# zxuno_rev_mcleod.net
KiCad netlist of a schematic drawn in EAGLE
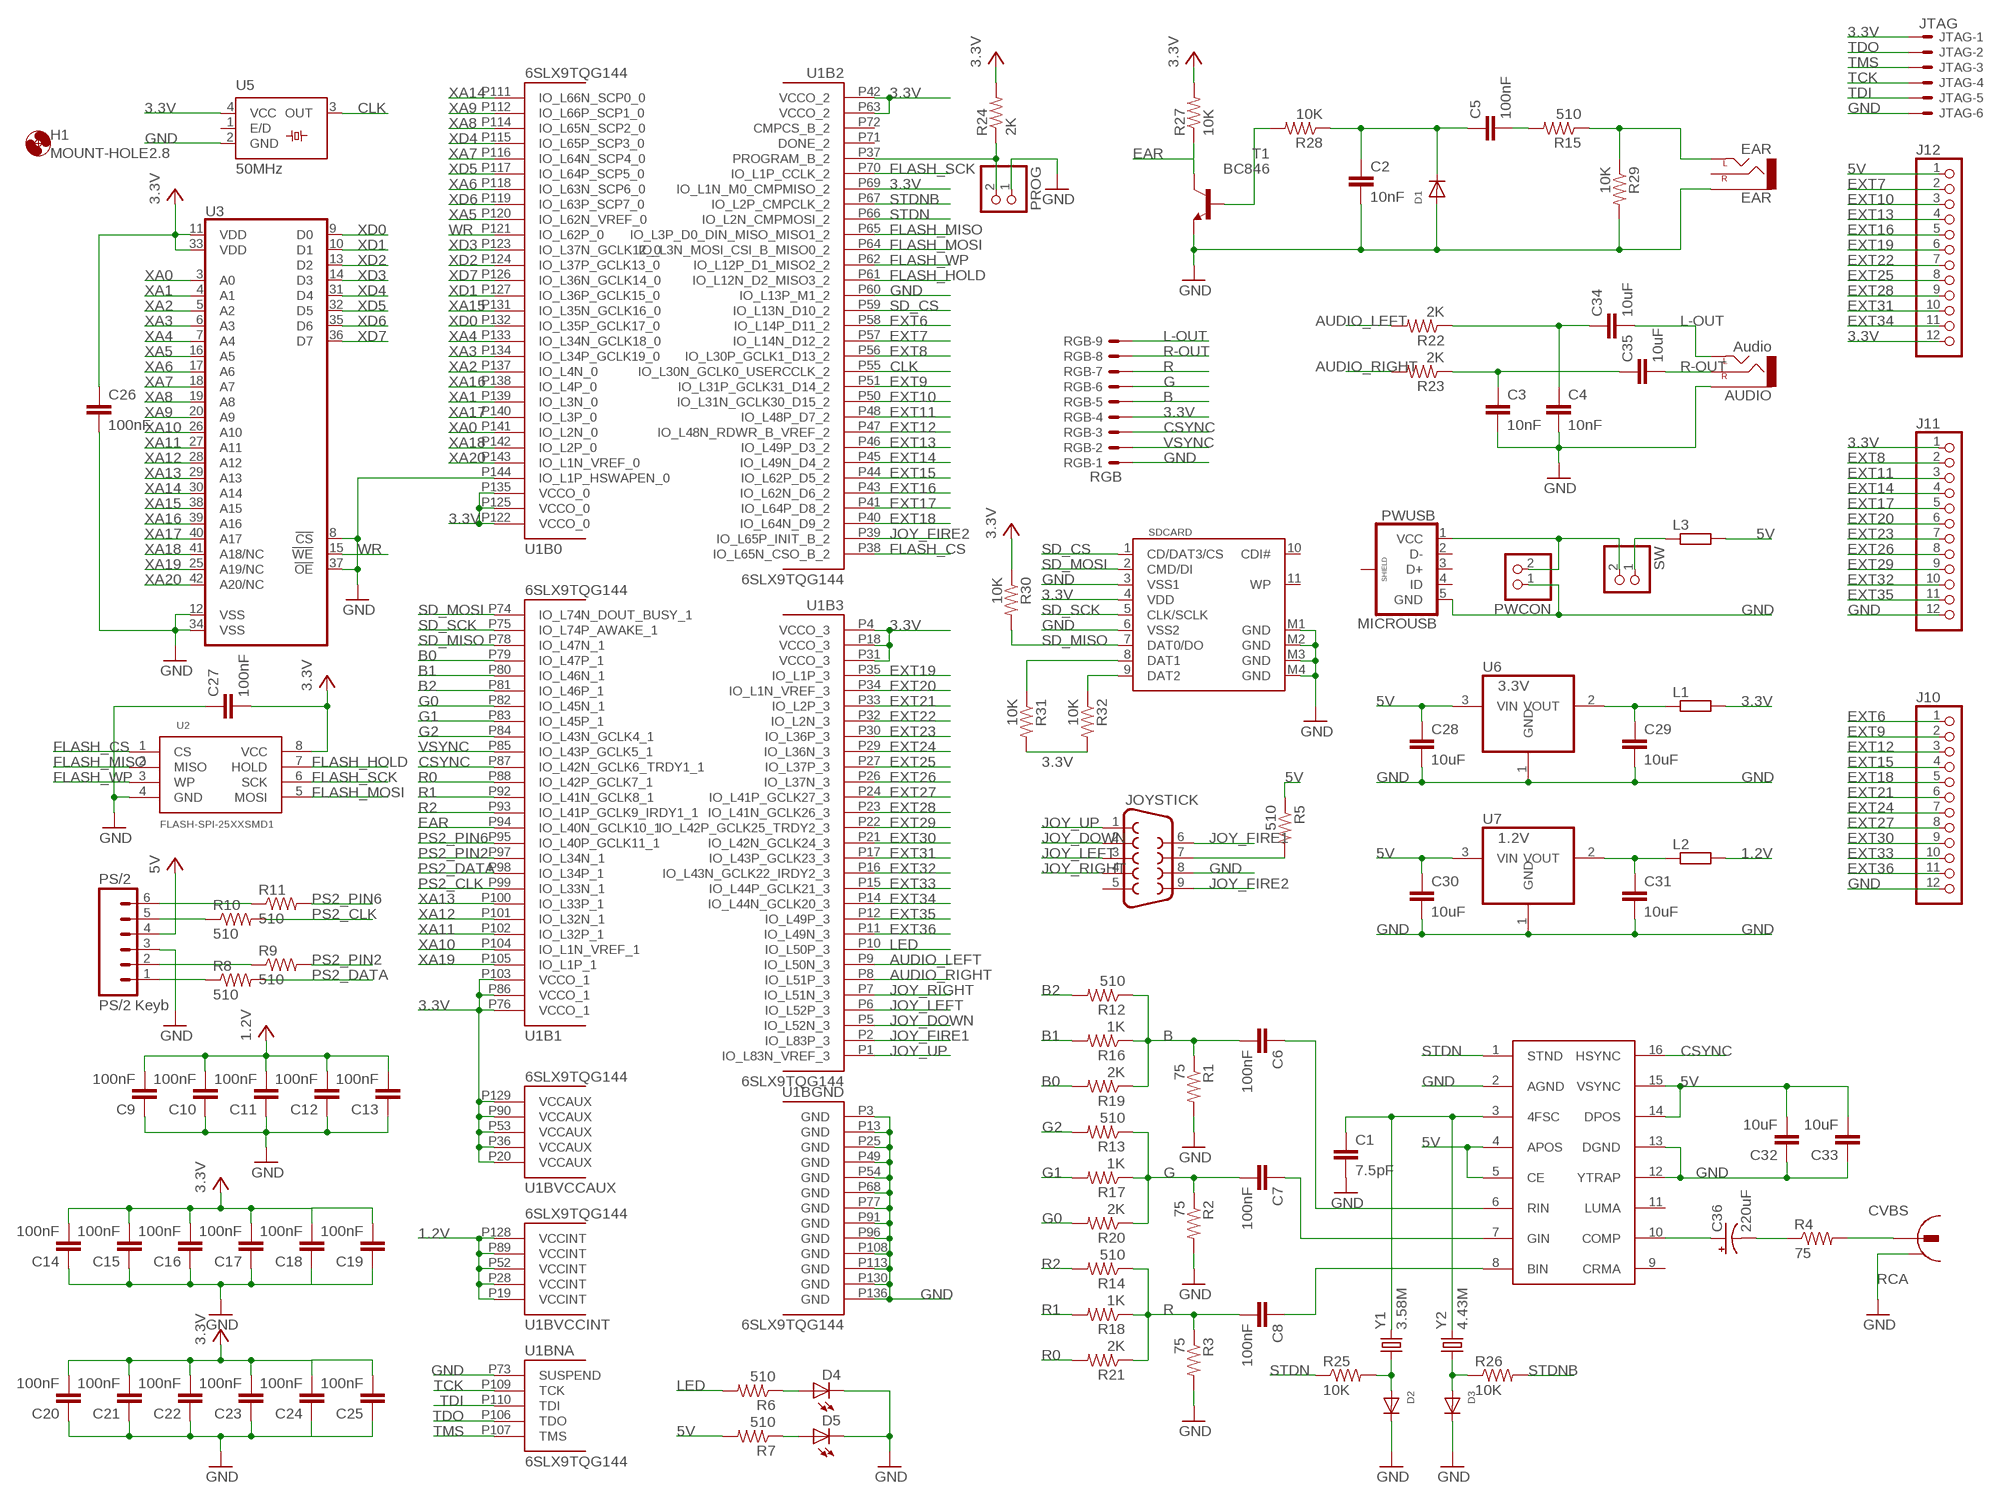
[diagram p0: schematic, sheet 1]

(export (version "E")
  (design (tool "Eeschema 10.0.6"))
  (components
    (comp (ref "AUDIO")
      (value "Audio")
      (footprint "eagle-import:AUDIO-JACK")
      (libsource (lib "eagle-import") (part "AUDIO-JACKPTH"))
    )
    (comp (ref "C1")
      (value "7.5pF")
      (footprint "eagle-import:C0805")
      (libsource (lib "eagle-import") (part "C-EUC0805"))
    )
    (comp (ref "C2")
      (value "10nF")
      (footprint "eagle-import:C0805")
      (libsource (lib "eagle-import") (part "C-EUC0805"))
    )
    (comp (ref "C3")
      (value "10nF")
      (footprint "eagle-import:C0805")
      (libsource (lib "eagle-import") (part "C-EUC0805"))
    )
    (comp (ref "C4")
      (value "10nF")
      (footprint "eagle-import:C0805")
      (libsource (lib "eagle-import") (part "C-EUC0805"))
    )
    (comp (ref "C5")
      (value "100nF")
      (footprint "eagle-import:C0603")
      (libsource (lib "eagle-import") (part "C-EUC0603"))
    )
    (comp (ref "C6")
      (value "100nF")
      (footprint "eagle-import:C0603")
      (libsource (lib "eagle-import") (part "C-EUC0603"))
    )
    (comp (ref "C7")
      (value "100nF")
      (footprint "eagle-import:C0603")
      (libsource (lib "eagle-import") (part "C-EUC0603"))
    )
    (comp (ref "C8")
      (value "100nF")
      (footprint "eagle-import:C0603")
      (libsource (lib "eagle-import") (part "C-EUC0603"))
    )
    (comp (ref "C9")
      (value "100nF")
      (footprint "eagle-import:C0603")
      (libsource (lib "eagle-import") (part "C-EUC0603"))
    )
    (comp (ref "C10")
      (value "100nF")
      (footprint "eagle-import:C0603")
      (libsource (lib "eagle-import") (part "C-EUC0603"))
    )
    (comp (ref "C11")
      (value "100nF")
      (footprint "eagle-import:C0603")
      (libsource (lib "eagle-import") (part "C-EUC0603"))
    )
    (comp (ref "C12")
      (value "100nF")
      (footprint "eagle-import:C0603")
      (libsource (lib "eagle-import") (part "C-EUC0603"))
    )
    (comp (ref "C13")
      (value "100nF")
      (footprint "eagle-import:C0603")
      (libsource (lib "eagle-import") (part "C-EUC0603"))
    )
    (comp (ref "C14")
      (value "100nF")
      (footprint "eagle-import:C0603")
      (libsource (lib "eagle-import") (part "C-EUC0603"))
    )
    (comp (ref "C15")
      (value "100nF")
      (footprint "eagle-import:C0603")
      (libsource (lib "eagle-import") (part "C-EUC0603"))
    )
    (comp (ref "C16")
      (value "100nF")
      (footprint "eagle-import:C0603")
      (libsource (lib "eagle-import") (part "C-EUC0603"))
    )
    (comp (ref "C17")
      (value "100nF")
      (footprint "eagle-import:C0603")
      (libsource (lib "eagle-import") (part "C-EUC0603"))
    )
    (comp (ref "C18")
      (value "100nF")
      (footprint "eagle-import:C0603")
      (libsource (lib "eagle-import") (part "C-EUC0603"))
    )
    (comp (ref "C19")
      (value "100nF")
      (footprint "eagle-import:C0603")
      (libsource (lib "eagle-import") (part "C-EUC0603"))
    )
    (comp (ref "C20")
      (value "100nF")
      (footprint "eagle-import:C0603")
      (libsource (lib "eagle-import") (part "C-EUC0603"))
    )
    (comp (ref "C21")
      (value "100nF")
      (footprint "eagle-import:C0603")
      (libsource (lib "eagle-import") (part "C-EUC0603"))
    )
    (comp (ref "C22")
      (value "100nF")
      (footprint "eagle-import:C0603")
      (libsource (lib "eagle-import") (part "C-EUC0603"))
    )
    (comp (ref "C23")
      (value "100nF")
      (footprint "eagle-import:C0603")
      (libsource (lib "eagle-import") (part "C-EUC0603"))
    )
    (comp (ref "C24")
      (value "100nF")
      (footprint "eagle-import:C0603")
      (libsource (lib "eagle-import") (part "C-EUC0603"))
    )
    (comp (ref "C25")
      (value "100nF")
      (footprint "eagle-import:C0603")
      (libsource (lib "eagle-import") (part "C-EUC0603"))
    )
    (comp (ref "C26")
      (value "100nF")
      (footprint "eagle-import:C0603")
      (libsource (lib "eagle-import") (part "C-EUC0603"))
    )
    (comp (ref "C27")
      (value "100nF")
      (footprint "eagle-import:C0603")
      (libsource (lib "eagle-import") (part "C-EUC0603"))
    )
    (comp (ref "C28")
      (value "10uF")
      (footprint "eagle-import:C0805")
      (libsource (lib "eagle-import") (part "C-EUC0805"))
    )
    (comp (ref "C29")
      (value "10uF")
      (footprint "eagle-import:C0805")
      (libsource (lib "eagle-import") (part "C-EUC0805"))
    )
    (comp (ref "C30")
      (value "10uF")
      (footprint "eagle-import:C0805")
      (libsource (lib "eagle-import") (part "C-EUC0805"))
    )
    (comp (ref "C31")
      (value "10uF")
      (footprint "eagle-import:C0805")
      (libsource (lib "eagle-import") (part "C-EUC0805"))
    )
    (comp (ref "C32")
      (value "10uF")
      (footprint "eagle-import:C0805")
      (libsource (lib "eagle-import") (part "C-EUC0805"))
    )
    (comp (ref "C33")
      (value "10uF")
      (footprint "eagle-import:C0805")
      (libsource (lib "eagle-import") (part "C-EUC0805"))
    )
    (comp (ref "C34")
      (value "10uF")
      (footprint "eagle-import:C0805")
      (libsource (lib "eagle-import") (part "C-EUC0805"))
    )
    (comp (ref "C35")
      (value "10uF")
      (footprint "eagle-import:C0805")
      (libsource (lib "eagle-import") (part "C-EUC0805"))
    )
    (comp (ref "C36")
      (value "220uF")
      (footprint "eagle-import:153CLV-0605")
      (libsource (lib "eagle-import") (part "CPOL-US153CLV-0605"))
    )
    (comp (ref "CVBS")
      (value "RCA")
      (footprint "eagle-import:RCA_JACK_RCJ-04X_-_DUPLICATE_1PRIMARY")
      (libsource (lib "eagle-import") (part "RCA_JACK_RCJ-04X_-_DUPLICATE_1"))
    )
    (comp (ref "D1")
      (value "DIODESOD-523")
      (footprint "eagle-import:SOD-523")
      (libsource (lib "eagle-import") (part "DIODESOD-523"))
    )
    (comp (ref "D2")
      (value "DIODESOD-523")
      (footprint "eagle-import:SOD-523")
      (libsource (lib "eagle-import") (part "DIODESOD-523"))
    )
    (comp (ref "D3")
      (value "DIODESOD-523")
      (footprint "eagle-import:SOD-523")
      (libsource (lib "eagle-import") (part "DIODESOD-523"))
    )
    (comp (ref "D4")
      (value "LEDCHIP-LED0805")
      (footprint "eagle-import:CHIP-LED0805")
      (libsource (lib "eagle-import") (part "LEDCHIP-LED0805"))
    )
    (comp (ref "D5")
      (value "LEDCHIP-LED0805")
      (footprint "eagle-import:CHIP-LED0805")
      (libsource (lib "eagle-import") (part "LEDCHIP-LED0805"))
    )
    (comp (ref "EAR")
      (value "EAR")
      (footprint "eagle-import:AUDIO-JACK")
      (libsource (lib "eagle-import") (part "AUDIO-JACKPTH"))
    )
    (comp (ref "H1")
      (value "MOUNT-HOLE2.8")
      (footprint "eagle-import:2,8")
      (libsource (lib "eagle-import") (part "MOUNT-HOLE2.8"))
    )
    (comp (ref "J10")
      (value "PINHD-1X12")
      (footprint "eagle-import:1X12")
      (libsource (lib "eagle-import") (part "PINHD-1X12"))
    )
    (comp (ref "J11")
      (value "PINHD-1X12")
      (footprint "eagle-import:1X12")
      (libsource (lib "eagle-import") (part "PINHD-1X12"))
    )
    (comp (ref "J12")
      (value "PINHD-1X12")
      (footprint "eagle-import:1X12")
      (libsource (lib "eagle-import") (part "PINHD-1X12"))
    )
    (comp (ref "JOYSTICK")
      (value "DB9MALE")
      (footprint "eagle-import:DB9_MALE")
      (libsource (lib "eagle-import") (part "DB9MALE"))
    )
    (comp (ref "JTAG")
      (value "JTAG")
      (footprint "eagle-import:53047-06")
      (fields (field (name "MPN") "53047-0610-C"))
      (libsource (lib "eagle-import") (part "53?-06047"))
    )
    (comp (ref "L1")
      (value "R-EU_M0805")
      (footprint "eagle-import:M0805")
      (libsource (lib "eagle-import") (part "R-EU_M0805"))
    )
    (comp (ref "L2")
      (value "R-EU_M0805")
      (footprint "eagle-import:M0805")
      (libsource (lib "eagle-import") (part "R-EU_M0805"))
    )
    (comp (ref "L3")
      (value "R-EU_M0805")
      (footprint "eagle-import:M0805")
      (libsource (lib "eagle-import") (part "R-EU_M0805"))
    )
    (comp (ref "PROG")
      (value "PINHD-1X2")
      (footprint "eagle-import:1X02")
      (libsource (lib "eagle-import") (part "PINHD-1X2"))
    )
    (comp (ref "PS/2")
      (value "PS/2 Keyb")
      (footprint "eagle-import:DINC_MIN_TM_6_1PRIMARY")
      (libsource (lib "eagle-import") (part "DINC_MIN_TM_6_1"))
    )
    (comp (ref "PWCON")
      (value "PINHD-1X2")
      (footprint "eagle-import:1X02")
      (libsource (lib "eagle-import") (part "PINHD-1X2"))
    )
    (comp (ref "PWUSB")
      (value "MICROUSB")
      (footprint "eagle-import:MICRO_USB_1PRIMARY")
      (libsource (lib "eagle-import") (part "MICROUSB"))
    )
    (comp (ref "R1")
      (value "75")
      (footprint "eagle-import:M0805")
      (libsource (lib "eagle-import") (part "R-US_M0805"))
    )
    (comp (ref "R2")
      (value "75")
      (footprint "eagle-import:M0805")
      (libsource (lib "eagle-import") (part "R-US_M0805"))
    )
    (comp (ref "R3")
      (value "75")
      (footprint "eagle-import:M0805")
      (libsource (lib "eagle-import") (part "R-US_M0805"))
    )
    (comp (ref "R4")
      (value "75")
      (footprint "eagle-import:M0805")
      (libsource (lib "eagle-import") (part "R-US_M0805"))
    )
    (comp (ref "R5")
      (value "510")
      (footprint "eagle-import:M0805")
      (libsource (lib "eagle-import") (part "R-US_M0805"))
    )
    (comp (ref "R6")
      (value "510")
      (footprint "eagle-import:M0805")
      (libsource (lib "eagle-import") (part "R-US_M0805"))
    )
    (comp (ref "R7")
      (value "510")
      (footprint "eagle-import:M0805")
      (libsource (lib "eagle-import") (part "R-US_M0805"))
    )
    (comp (ref "R8")
      (value "510")
      (footprint "eagle-import:M0805")
      (libsource (lib "eagle-import") (part "R-US_M0805"))
    )
    (comp (ref "R9")
      (value "510")
      (footprint "eagle-import:M0805")
      (libsource (lib "eagle-import") (part "R-US_M0805"))
    )
    (comp (ref "R10")
      (value "510")
      (footprint "eagle-import:M0805")
      (libsource (lib "eagle-import") (part "R-US_M0805"))
    )
    (comp (ref "R11")
      (value "510")
      (footprint "eagle-import:M0805")
      (libsource (lib "eagle-import") (part "R-US_M0805"))
    )
    (comp (ref "R12")
      (value "510")
      (footprint "eagle-import:M0805")
      (libsource (lib "eagle-import") (part "R-US_M0805"))
    )
    (comp (ref "R13")
      (value "510")
      (footprint "eagle-import:M0805")
      (libsource (lib "eagle-import") (part "R-US_M0805"))
    )
    (comp (ref "R14")
      (value "510")
      (footprint "eagle-import:M0805")
      (libsource (lib "eagle-import") (part "R-US_M0805"))
    )
    (comp (ref "R15")
      (value "510")
      (footprint "eagle-import:M0805")
      (libsource (lib "eagle-import") (part "R-US_M0805"))
    )
    (comp (ref "R16")
      (value "1K")
      (footprint "eagle-import:M0805")
      (libsource (lib "eagle-import") (part "R-US_M0805"))
    )
    (comp (ref "R17")
      (value "1K")
      (footprint "eagle-import:M0805")
      (libsource (lib "eagle-import") (part "R-US_M0805"))
    )
    (comp (ref "R18")
      (value "1K")
      (footprint "eagle-import:M0805")
      (libsource (lib "eagle-import") (part "R-US_M0805"))
    )
    (comp (ref "R19")
      (value "2K")
      (footprint "eagle-import:M0805")
      (libsource (lib "eagle-import") (part "R-US_M0805"))
    )
    (comp (ref "R20")
      (value "2K")
      (footprint "eagle-import:M0805")
      (libsource (lib "eagle-import") (part "R-US_M0805"))
    )
    (comp (ref "R21")
      (value "2K")
      (footprint "eagle-import:M0805")
      (libsource (lib "eagle-import") (part "R-US_M0805"))
    )
    (comp (ref "R22")
      (value "2K")
      (footprint "eagle-import:M0805")
      (libsource (lib "eagle-import") (part "R-US_M0805"))
    )
    (comp (ref "R23")
      (value "2K")
      (footprint "eagle-import:M0805")
      (libsource (lib "eagle-import") (part "R-US_M0805"))
    )
    (comp (ref "R24")
      (value "2K")
      (footprint "eagle-import:M0805")
      (libsource (lib "eagle-import") (part "R-US_M0805"))
    )
    (comp (ref "R25")
      (value "10K")
      (footprint "eagle-import:M0805")
      (libsource (lib "eagle-import") (part "R-US_M0805"))
    )
    (comp (ref "R26")
      (value "10K")
      (footprint "eagle-import:M0805")
      (libsource (lib "eagle-import") (part "R-US_M0805"))
    )
    (comp (ref "R27")
      (value "10K")
      (footprint "eagle-import:M0805")
      (libsource (lib "eagle-import") (part "R-US_M0805"))
    )
    (comp (ref "R28")
      (value "10K")
      (footprint "eagle-import:M0805")
      (libsource (lib "eagle-import") (part "R-US_M0805"))
    )
    (comp (ref "R29")
      (value "10K")
      (footprint "eagle-import:M0805")
      (libsource (lib "eagle-import") (part "R-US_M0805"))
    )
    (comp (ref "R30")
      (value "10K")
      (footprint "eagle-import:M0805")
      (libsource (lib "eagle-import") (part "R-US_M0805"))
    )
    (comp (ref "R31")
      (value "10K")
      (footprint "eagle-import:M0805")
      (libsource (lib "eagle-import") (part "R-US_M0805"))
    )
    (comp (ref "R32")
      (value "10K")
      (footprint "eagle-import:M0805")
      (libsource (lib "eagle-import") (part "R-US_M0805"))
    )
    (comp (ref "RGB")
      (value "RGB")
      (footprint "eagle-import:53048-09")
      (fields (field (name "MPN") "53048-0910"))
      (libsource (lib "eagle-import") (part "53?-09048"))
    )
    (comp (ref "SDCARD")
      (value "SDCARD")
      (footprint "eagle-import:SDCMF-10915W010")
      (libsource (lib "eagle-import") (part "SDCARD"))
    )
    (comp (ref "SW")
      (value "PINHD-1X2")
      (footprint "eagle-import:1X02")
      (libsource (lib "eagle-import") (part "PINHD-1X2"))
    )
    (comp (ref "T1")
      (value "BC846")
      (footprint "eagle-import:SOT23")
      (libsource (lib "eagle-import") (part "BC846"))
    )
    (comp (ref "U1")
      (value "6SLX9TQG144")
      (footprint "eagle-import:TQ144")
      (libsource (lib "eagle-import") (part "6SLX9TQG144"))
    )
    (comp (ref "U2")
      (value "FLASH-SPI-25XXSMD1")
      (footprint "eagle-import:SO08-EIAJ")
      (libsource (lib "eagle-import") (part "FLASH-SPI-25XXSMD1"))
    )
    (comp (ref "U3")
      (value "ISSI_SRAM_8BIT")
      (footprint "eagle-import:TSOP44-II")
      (libsource (lib "eagle-import") (part "ISSI_SRAM_8BIT"))
    )
    (comp (ref "U4")
      (value "AD724")
      (footprint "eagle-import:SO16W")
      (libsource (lib "eagle-import") (part "AD725"))
    )
    (comp (ref "U5")
      (value "50MHz")
      (footprint "eagle-import:SM_OSC_1PRIMARY")
      (libsource (lib "eagle-import") (part "SM_OSC_1"))
    )
    (comp (ref "U6")
      (value "3.3V")
      (footprint "eagle-import:SOT223")
      (fields (field (name "MPN") "REG1117"))
      (libsource (lib "eagle-import") (part "REG1117"))
    )
    (comp (ref "U7")
      (value "1.2V")
      (footprint "eagle-import:SOT223")
      (fields (field (name "MPN") "REG1117"))
      (libsource (lib "eagle-import") (part "REG1117"))
    )
    (comp (ref "Y1")
      (value "3.58M")
      (footprint "eagle-import:HC49UP")
      (libsource (lib "eagle-import") (part "CRYSTALHC49UP"))
    )
    (comp (ref "Y2")
      (value "4.43M")
      (footprint "eagle-import:HC49UP")
      (libsource (lib "eagle-import") (part "CRYSTALHC49UP"))
    )
  )
  (nets
    (net (code "1") (name "/AUDIO_LEFT") (class "Default")
      (node (ref "R22") (pin "2") (pinfunction "2_2") (pintype "passive"))
      (node (ref "U1") (pin "P9") (pinfunction "IO_L50N_3_P9") (pintype "bidirectional"))
    )
    (net (code "2") (name "/AUDIO_RIGHT") (class "Default")
      (node (ref "R23") (pin "2") (pinfunction "2_2") (pintype "passive"))
      (node (ref "U1") (pin "P8") (pinfunction "IO_L51P_3_P8") (pintype "bidirectional"))
    )
    (net (code "3") (name "/B") (class "Default")
      (node (ref "C6") (pin "2") (pinfunction "2_2") (pintype "passive"))
      (node (ref "R1") (pin "1") (pinfunction "1_1") (pintype "passive"))
      (node (ref "R12") (pin "1") (pinfunction "1_1") (pintype "passive"))
      (node (ref "R16") (pin "1") (pinfunction "1_1") (pintype "passive"))
      (node (ref "R19") (pin "1") (pinfunction "1_1") (pintype "passive"))
      (node (ref "RGB") (pin "5") (pinfunction "S_5") (pintype "passive"))
    )
    (net (code "4") (name "/B0") (class "Default")
      (node (ref "R19") (pin "2") (pinfunction "2_2") (pintype "passive"))
      (node (ref "U1") (pin "P79") (pinfunction "IO_L47P_1_P79") (pintype "bidirectional"))
    )
    (net (code "5") (name "/B1") (class "Default")
      (node (ref "R16") (pin "2") (pinfunction "2_2") (pintype "passive"))
      (node (ref "U1") (pin "P80") (pinfunction "IO_L46N_1_P80") (pintype "bidirectional"))
    )
    (net (code "6") (name "/B2") (class "Default")
      (node (ref "R12") (pin "2") (pinfunction "2_2") (pintype "passive"))
      (node (ref "U1") (pin "P81") (pinfunction "IO_L46P_1_P81") (pintype "bidirectional"))
    )
    (net (code "7") (name "/CLK") (class "Default")
      (node (ref "U1") (pin "P55") (pinfunction "IO_L30N_GCLK0_USERCCLK_2_P55") (pintype "bidirectional"))
      (node (ref "U5") (pin "3") (pinfunction "OUT_3") (pintype "output"))
    )
    (net (code "8") (name "/CSYNC") (class "Default")
      (node (ref "RGB") (pin "3") (pinfunction "S_3") (pintype "passive"))
      (node (ref "U1") (pin "P87") (pinfunction "IO_L42N_GCLK6_TRDY1_1_P87") (pintype "bidirectional"))
      (node (ref "U4") (pin "16") (pinfunction "HSYNC_16") (pintype "bidirectional"))
    )
    (net (code "9") (name "/EAR") (class "Default")
      (node (ref "R27") (pin "1") (pinfunction "1_1") (pintype "passive"))
      (node (ref "T1") (pin "3") (pinfunction "C_3") (pintype "passive"))
      (node (ref "U1") (pin "P94") (pinfunction "IO_L40N_GCLK10_1_P94") (pintype "bidirectional"))
    )
    (net (code "10") (name "/EXT6") (class "Default")
      (node (ref "J10") (pin "1") (pinfunction "1_1") (pintype "passive"))
      (node (ref "U1") (pin "P58") (pinfunction "IO_L14P_D11_2_P58") (pintype "bidirectional"))
    )
    (net (code "11") (name "/EXT7") (class "Default")
      (node (ref "J12") (pin "2") (pinfunction "2_2") (pintype "passive"))
      (node (ref "U1") (pin "P57") (pinfunction "IO_L14N_D12_2_P57") (pintype "bidirectional"))
    )
    (net (code "12") (name "/EXT8") (class "Default")
      (node (ref "J11") (pin "2") (pinfunction "2_2") (pintype "passive"))
      (node (ref "U1") (pin "P56") (pinfunction "IO_L30P_GCLK1_D13_2_P56") (pintype "bidirectional"))
    )
    (net (code "13") (name "/EXT9") (class "Default")
      (node (ref "J10") (pin "2") (pinfunction "2_2") (pintype "passive"))
      (node (ref "U1") (pin "P51") (pinfunction "IO_L31P_GCLK31_D14_2_P51") (pintype "bidirectional"))
    )
    (net (code "14") (name "/EXT10") (class "Default")
      (node (ref "J12") (pin "3") (pinfunction "3_3") (pintype "passive"))
      (node (ref "U1") (pin "P50") (pinfunction "IO_L31N_GCLK30_D15_2_P50") (pintype "bidirectional"))
    )
    (net (code "15") (name "/EXT11") (class "Default")
      (node (ref "J11") (pin "3") (pinfunction "3_3") (pintype "passive"))
      (node (ref "U1") (pin "P48") (pinfunction "IO_L48P_D7_2_P48") (pintype "bidirectional"))
    )
    (net (code "16") (name "/EXT12") (class "Default")
      (node (ref "J10") (pin "3") (pinfunction "3_3") (pintype "passive"))
      (node (ref "U1") (pin "P47") (pinfunction "IO_L48N_RDWR_B_VREF_2_P47") (pintype "bidirectional"))
    )
    (net (code "17") (name "/EXT13") (class "Default")
      (node (ref "J12") (pin "4") (pinfunction "4_4") (pintype "passive"))
      (node (ref "U1") (pin "P46") (pinfunction "IO_L49P_D3_2_P46") (pintype "bidirectional"))
    )
    (net (code "18") (name "/EXT14") (class "Default")
      (node (ref "J11") (pin "4") (pinfunction "4_4") (pintype "passive"))
      (node (ref "U1") (pin "P45") (pinfunction "IO_L49N_D4_2_P45") (pintype "bidirectional"))
    )
    (net (code "19") (name "/EXT15") (class "Default")
      (node (ref "J10") (pin "4") (pinfunction "4_4") (pintype "passive"))
      (node (ref "U1") (pin "P44") (pinfunction "IO_L62P_D5_2_P44") (pintype "bidirectional"))
    )
    (net (code "20") (name "/EXT16") (class "Default")
      (node (ref "J12") (pin "5") (pinfunction "5_5") (pintype "passive"))
      (node (ref "U1") (pin "P43") (pinfunction "IO_L62N_D6_2_P43") (pintype "bidirectional"))
    )
    (net (code "21") (name "/EXT17") (class "Default")
      (node (ref "J11") (pin "5") (pinfunction "5_5") (pintype "passive"))
      (node (ref "U1") (pin "P41") (pinfunction "IO_L64P_D8_2_P41") (pintype "bidirectional"))
    )
    (net (code "22") (name "/EXT18") (class "Default")
      (node (ref "J10") (pin "5") (pinfunction "5_5") (pintype "passive"))
      (node (ref "U1") (pin "P40") (pinfunction "IO_L64N_D9_2_P40") (pintype "bidirectional"))
    )
    (net (code "23") (name "/EXT19") (class "Default")
      (node (ref "J12") (pin "6") (pinfunction "6_6") (pintype "passive"))
      (node (ref "U1") (pin "P35") (pinfunction "IO_L1P_3_P35") (pintype "bidirectional"))
    )
    (net (code "24") (name "/EXT20") (class "Default")
      (node (ref "J11") (pin "6") (pinfunction "6_6") (pintype "passive"))
      (node (ref "U1") (pin "P34") (pinfunction "IO_L1N_VREF_3_P34") (pintype "bidirectional"))
    )
    (net (code "25") (name "/EXT21") (class "Default")
      (node (ref "J10") (pin "6") (pinfunction "6_6") (pintype "passive"))
      (node (ref "U1") (pin "P33") (pinfunction "IO_L2P_3_P33") (pintype "bidirectional"))
    )
    (net (code "26") (name "/EXT22") (class "Default")
      (node (ref "J12") (pin "7") (pinfunction "7_7") (pintype "passive"))
      (node (ref "U1") (pin "P32") (pinfunction "IO_L2N_3_P32") (pintype "bidirectional"))
    )
    (net (code "27") (name "/EXT23") (class "Default")
      (node (ref "J11") (pin "7") (pinfunction "7_7") (pintype "passive"))
      (node (ref "U1") (pin "P30") (pinfunction "IO_L36P_3_P30") (pintype "bidirectional"))
    )
    (net (code "28") (name "/EXT24") (class "Default")
      (node (ref "J10") (pin "7") (pinfunction "7_7") (pintype "passive"))
      (node (ref "U1") (pin "P29") (pinfunction "IO_L36N_3_P29") (pintype "bidirectional"))
    )
    (net (code "29") (name "/EXT25") (class "Default")
      (node (ref "J12") (pin "8") (pinfunction "8_8") (pintype "passive"))
      (node (ref "U1") (pin "P27") (pinfunction "IO_L37P_3_P27") (pintype "bidirectional"))
    )
    (net (code "30") (name "/EXT26") (class "Default")
      (node (ref "J11") (pin "8") (pinfunction "8_8") (pintype "passive"))
      (node (ref "U1") (pin "P26") (pinfunction "IO_L37N_3_P26") (pintype "bidirectional"))
    )
    (net (code "31") (name "/EXT27") (class "Default")
      (node (ref "J10") (pin "8") (pinfunction "8_8") (pintype "passive"))
      (node (ref "U1") (pin "P24") (pinfunction "IO_L41P_GCLK27_3_P24") (pintype "bidirectional"))
    )
    (net (code "32") (name "/EXT28") (class "Default")
      (node (ref "J12") (pin "9") (pinfunction "9_9") (pintype "passive"))
      (node (ref "U1") (pin "P23") (pinfunction "IO_L41N_GCLK26_3_P23") (pintype "bidirectional"))
    )
    (net (code "33") (name "/EXT29") (class "Default")
      (node (ref "J11") (pin "9") (pinfunction "9_9") (pintype "passive"))
      (node (ref "U1") (pin "P22") (pinfunction "IO_L42P_GCLK25_TRDY2_3_P22") (pintype "bidirectional"))
    )
    (net (code "34") (name "/EXT30") (class "Default")
      (node (ref "J10") (pin "9") (pinfunction "9_9") (pintype "passive"))
      (node (ref "U1") (pin "P21") (pinfunction "IO_L42N_GCLK24_3_P21") (pintype "bidirectional"))
    )
    (net (code "35") (name "/EXT31") (class "Default")
      (node (ref "J12") (pin "10") (pinfunction "10_10") (pintype "passive"))
      (node (ref "U1") (pin "P17") (pinfunction "IO_L43P_GCLK23_3_P17") (pintype "bidirectional"))
    )
    (net (code "36") (name "/EXT32") (class "Default")
      (node (ref "J11") (pin "10") (pinfunction "10_10") (pintype "passive"))
      (node (ref "U1") (pin "P16") (pinfunction "IO_L43N_GCLK22_IRDY2_3_P16") (pintype "bidirectional"))
    )
    (net (code "37") (name "/EXT33") (class "Default")
      (node (ref "J10") (pin "10") (pinfunction "10_10") (pintype "passive"))
      (node (ref "U1") (pin "P15") (pinfunction "IO_L44P_GCLK21_3_P15") (pintype "bidirectional"))
    )
    (net (code "38") (name "/EXT34") (class "Default")
      (node (ref "J12") (pin "11") (pinfunction "11_11") (pintype "passive"))
      (node (ref "U1") (pin "P14") (pinfunction "IO_L44N_GCLK20_3_P14") (pintype "bidirectional"))
    )
    (net (code "39") (name "/EXT35") (class "Default")
      (node (ref "J11") (pin "11") (pinfunction "11_11") (pintype "passive"))
      (node (ref "U1") (pin "P12") (pinfunction "IO_L49P_3_P12") (pintype "bidirectional"))
    )
    (net (code "40") (name "/EXT36") (class "Default")
      (node (ref "J10") (pin "11") (pinfunction "11_11") (pintype "passive"))
      (node (ref "U1") (pin "P11") (pinfunction "IO_L49N_3_P11") (pintype "bidirectional"))
    )
    (net (code "41") (name "/FLASH_CS") (class "Default")
      (node (ref "U1") (pin "P38") (pinfunction "IO_L65N_CSO_B_2_P38") (pintype "bidirectional"))
      (node (ref "U2") (pin "1") (pinfunction "CS_1") (pintype "bidirectional"))
    )
    (net (code "42") (name "/FLASH_HOLD") (class "Default")
      (node (ref "U1") (pin "P61") (pinfunction "IO_L12N_D2_MISO3_2_P61") (pintype "bidirectional"))
      (node (ref "U2") (pin "7") (pinfunction "HOLD_7") (pintype "bidirectional"))
    )
    (net (code "43") (name "/FLASH_MISO") (class "Default")
      (node (ref "U1") (pin "P65") (pinfunction "IO_L3P_D0_DIN_MISO_MISO1_2_P65") (pintype "bidirectional"))
      (node (ref "U2") (pin "2") (pinfunction "MISO_2") (pintype "bidirectional"))
    )
    (net (code "44") (name "/FLASH_MOSI") (class "Default")
      (node (ref "U1") (pin "P64") (pinfunction "IO_L3N_MOSI_CSI_B_MISO0_2_P64") (pintype "bidirectional"))
      (node (ref "U2") (pin "5") (pinfunction "MOSI_5") (pintype "bidirectional"))
    )
    (net (code "45") (name "/FLASH_SCK") (class "Default")
      (node (ref "U1") (pin "P70") (pinfunction "IO_L1P_CCLK_2_P70") (pintype "bidirectional"))
      (node (ref "U2") (pin "6") (pinfunction "SCK_6") (pintype "bidirectional"))
    )
    (net (code "46") (name "/FLASH_WP") (class "Default")
      (node (ref "U1") (pin "P62") (pinfunction "IO_L12P_D1_MISO2_2_P62") (pintype "bidirectional"))
      (node (ref "U2") (pin "3") (pinfunction "WP_3") (pintype "bidirectional"))
    )
    (net (code "47") (name "/G") (class "Default")
      (node (ref "C7") (pin "2") (pinfunction "2_2") (pintype "passive"))
      (node (ref "R13") (pin "1") (pinfunction "1_1") (pintype "passive"))
      (node (ref "R17") (pin "1") (pinfunction "1_1") (pintype "passive"))
      (node (ref "R2") (pin "1") (pinfunction "1_1") (pintype "passive"))
      (node (ref "R20") (pin "1") (pinfunction "1_1") (pintype "passive"))
      (node (ref "RGB") (pin "6") (pinfunction "S_6") (pintype "passive"))
    )
    (net (code "48") (name "/G0") (class "Default")
      (node (ref "R20") (pin "2") (pinfunction "2_2") (pintype "passive"))
      (node (ref "U1") (pin "P82") (pinfunction "IO_L45N_1_P82") (pintype "bidirectional"))
    )
    (net (code "49") (name "/G1") (class "Default")
      (node (ref "R17") (pin "2") (pinfunction "2_2") (pintype "passive"))
      (node (ref "U1") (pin "P83") (pinfunction "IO_L45P_1_P83") (pintype "bidirectional"))
    )
    (net (code "50") (name "/G2") (class "Default")
      (node (ref "R13") (pin "2") (pinfunction "2_2") (pintype "passive"))
      (node (ref "U1") (pin "P84") (pinfunction "IO_L43N_GCLK4_1_P84") (pintype "bidirectional"))
    )
    (net (code "51") (name "/JOY_DOWN") (class "Default")
      (node (ref "JOYSTICK") (pin "2") (pinfunction "2_2") (pintype "passive"))
      (node (ref "U1") (pin "P5") (pinfunction "IO_L52N_3_P5") (pintype "bidirectional"))
    )
    (net (code "52") (name "/JOY_FIRE1") (class "Default")
      (node (ref "JOYSTICK") (pin "6") (pinfunction "6_6") (pintype "passive"))
      (node (ref "U1") (pin "P2") (pinfunction "IO_L83P_3_P2") (pintype "bidirectional"))
    )
    (net (code "53") (name "/JOY_FIRE2") (class "Default")
      (node (ref "JOYSTICK") (pin "9") (pinfunction "9_9") (pintype "passive"))
      (node (ref "U1") (pin "P39") (pinfunction "IO_L65P_INIT_B_2_P39") (pintype "bidirectional"))
    )
    (net (code "54") (name "/JOY_LEFT") (class "Default")
      (node (ref "JOYSTICK") (pin "3") (pinfunction "3_3") (pintype "passive"))
      (node (ref "U1") (pin "P6") (pinfunction "IO_L52P_3_P6") (pintype "bidirectional"))
    )
    (net (code "55") (name "/JOY_RIGHT") (class "Default")
      (node (ref "JOYSTICK") (pin "4") (pinfunction "4_4") (pintype "passive"))
      (node (ref "U1") (pin "P7") (pinfunction "IO_L51N_3_P7") (pintype "bidirectional"))
    )
    (net (code "56") (name "/JOY_UP") (class "Default")
      (node (ref "JOYSTICK") (pin "1") (pinfunction "1_1") (pintype "passive"))
      (node (ref "U1") (pin "P1") (pinfunction "IO_L83N_VREF_3_P1") (pintype "bidirectional"))
    )
    (net (code "57") (name "/L-OUT") (class "Default")
      (node (ref "AUDIO") (pin "TIP") (pinfunction "LEFT_TIP") (pintype "bidirectional"))
      (node (ref "C34") (pin "2") (pinfunction "2_2") (pintype "passive"))
      (node (ref "RGB") (pin "9") (pinfunction "S_9") (pintype "passive"))
    )
    (net (code "58") (name "/LED") (class "Default")
      (node (ref "R6") (pin "2") (pinfunction "2_2") (pintype "passive"))
      (node (ref "U1") (pin "P10") (pinfunction "IO_L50P_3_P10") (pintype "bidirectional"))
    )
    (net (code "59") (name "/PS2_CLK") (class "Default")
      (node (ref "R10") (pin "2") (pinfunction "2_2") (pintype "passive"))
      (node (ref "U1") (pin "P99") (pinfunction "IO_L33N_1_P99") (pintype "bidirectional"))
    )
    (net (code "60") (name "/PS2_DATA") (class "Default")
      (node (ref "R8") (pin "2") (pinfunction "2_2") (pintype "passive"))
      (node (ref "U1") (pin "P98") (pinfunction "IO_L34P_1_P98") (pintype "bidirectional"))
    )
    (net (code "61") (name "/PS2_PIN2") (class "Default")
      (node (ref "R9") (pin "2") (pinfunction "2_2") (pintype "passive"))
      (node (ref "U1") (pin "P97") (pinfunction "IO_L34N_1_P97") (pintype "bidirectional"))
    )
    (net (code "62") (name "/PS2_PIN6") (class "Default")
      (node (ref "R11") (pin "2") (pinfunction "2_2") (pintype "passive"))
      (node (ref "U1") (pin "P95") (pinfunction "IO_L40P_GCLK11_1_P95") (pintype "bidirectional"))
    )
    (net (code "63") (name "/R") (class "Default")
      (node (ref "C8") (pin "2") (pinfunction "2_2") (pintype "passive"))
      (node (ref "R14") (pin "1") (pinfunction "1_1") (pintype "passive"))
      (node (ref "R18") (pin "1") (pinfunction "1_1") (pintype "passive"))
      (node (ref "R21") (pin "1") (pinfunction "1_1") (pintype "passive"))
      (node (ref "R3") (pin "1") (pinfunction "1_1") (pintype "passive"))
      (node (ref "RGB") (pin "7") (pinfunction "S_7") (pintype "passive"))
    )
    (net (code "64") (name "/R-OUT") (class "Default")
      (node (ref "AUDIO") (pin "RING") (pinfunction "RIGHT_RING") (pintype "bidirectional"))
      (node (ref "C35") (pin "2") (pinfunction "2_2") (pintype "passive"))
      (node (ref "RGB") (pin "8") (pinfunction "S_8") (pintype "passive"))
    )
    (net (code "65") (name "/R0") (class "Default")
      (node (ref "R21") (pin "2") (pinfunction "2_2") (pintype "passive"))
      (node (ref "U1") (pin "P88") (pinfunction "IO_L42P_GCLK7_1_P88") (pintype "bidirectional"))
    )
    (net (code "66") (name "/R1") (class "Default")
      (node (ref "R18") (pin "2") (pinfunction "2_2") (pintype "passive"))
      (node (ref "U1") (pin "P92") (pinfunction "IO_L41N_GCLK8_1_P92") (pintype "bidirectional"))
    )
    (net (code "67") (name "/R2") (class "Default")
      (node (ref "R14") (pin "2") (pinfunction "2_2") (pintype "passive"))
      (node (ref "U1") (pin "P93") (pinfunction "IO_L41P_GCLK9_IRDY1_1_P93") (pintype "bidirectional"))
    )
    (net (code "68") (name "/SD_CS") (class "Default")
      (node (ref "SDCARD") (pin "1") (pinfunction "CD/DAT3/CS_1") (pintype "bidirectional"))
      (node (ref "U1") (pin "P59") (pinfunction "IO_L13N_D10_2_P59") (pintype "bidirectional"))
    )
    (net (code "69") (name "/SD_MISO") (class "Default")
      (node (ref "R30") (pin "2") (pinfunction "2_2") (pintype "passive"))
      (node (ref "SDCARD") (pin "7") (pinfunction "DAT0/DO_7") (pintype "bidirectional"))
      (node (ref "U1") (pin "P78") (pinfunction "IO_L47N_1_P78") (pintype "bidirectional"))
    )
    (net (code "70") (name "/SD_MOSI") (class "Default")
      (node (ref "SDCARD") (pin "2") (pinfunction "CMD/DI_2") (pintype "bidirectional"))
      (node (ref "U1") (pin "P74") (pinfunction "IO_L74N_DOUT_BUSY_1_P74") (pintype "bidirectional"))
    )
    (net (code "71") (name "/SD_SCK") (class "Default")
      (node (ref "SDCARD") (pin "5") (pinfunction "CLK/SCLK_5") (pintype "bidirectional"))
      (node (ref "U1") (pin "P75") (pinfunction "IO_L74P_AWAKE_1_P75") (pintype "bidirectional"))
    )
    (net (code "72") (name "/STDN") (class "Default")
      (node (ref "R25") (pin "1") (pinfunction "1_1") (pintype "passive"))
      (node (ref "U1") (pin "P66") (pinfunction "IO_L2N_CMPMOSI_2_P66") (pintype "bidirectional"))
      (node (ref "U4") (pin "1") (pinfunction "STND_1") (pintype "bidirectional"))
    )
    (net (code "73") (name "/STDNB") (class "Default")
      (node (ref "R26") (pin "2") (pinfunction "2_2") (pintype "passive"))
      (node (ref "U1") (pin "P67") (pinfunction "IO_L2P_CMPCLK_2_P67") (pintype "bidirectional"))
    )
    (net (code "74") (name "/TCK") (class "Default")
      (node (ref "JTAG") (pin "4") (pinfunction "S_4") (pintype "passive"))
      (node (ref "U1") (pin "P109") (pinfunction "TCK_P109") (pintype "input"))
    )
    (net (code "75") (name "/TDI") (class "Default")
      (node (ref "JTAG") (pin "5") (pinfunction "S_5") (pintype "passive"))
      (node (ref "U1") (pin "P110") (pinfunction "TDI_P110") (pintype "input"))
    )
    (net (code "76") (name "/TDO") (class "Default")
      (node (ref "JTAG") (pin "2") (pinfunction "S_2") (pintype "passive"))
      (node (ref "U1") (pin "P106") (pinfunction "TDO_P106") (pintype "output"))
    )
    (net (code "77") (name "/TMS") (class "Default")
      (node (ref "JTAG") (pin "3") (pinfunction "S_3") (pintype "passive"))
      (node (ref "U1") (pin "P107") (pinfunction "TMS_P107") (pintype "input"))
    )
    (net (code "78") (name "/VSYNC") (class "Default")
      (node (ref "RGB") (pin "2") (pinfunction "S_2") (pintype "passive"))
      (node (ref "U1") (pin "P85") (pinfunction "IO_L43P_GCLK5_1_P85") (pintype "bidirectional"))
    )
    (net (code "79") (name "/WR") (class "Default")
      (node (ref "U1") (pin "P121") (pinfunction "IO_L62P_0_P121") (pintype "bidirectional"))
      (node (ref "U3") (pin "15") (pinfunction "~{WE}_15") (pintype "input"))
    )
    (net (code "80") (name "/XA0") (class "Default")
      (node (ref "U1") (pin "P141") (pinfunction "IO_L2N_0_P141") (pintype "bidirectional"))
      (node (ref "U3") (pin "3") (pinfunction "A0_3") (pintype "input"))
    )
    (net (code "81") (name "/XA1") (class "Default")
      (node (ref "U1") (pin "P139") (pinfunction "IO_L3N_0_P139") (pintype "bidirectional"))
      (node (ref "U3") (pin "4") (pinfunction "A1_4") (pintype "input"))
    )
    (net (code "82") (name "/XA2") (class "Default")
      (node (ref "U1") (pin "P137") (pinfunction "IO_L4N_0_P137") (pintype "bidirectional"))
      (node (ref "U3") (pin "5") (pinfunction "A2_5") (pintype "input"))
    )
    (net (code "83") (name "/XA3") (class "Default")
      (node (ref "U1") (pin "P134") (pinfunction "IO_L34P_GCLK19_0_P134") (pintype "bidirectional"))
      (node (ref "U3") (pin "6") (pinfunction "A3_6") (pintype "input"))
    )
    (net (code "84") (name "/XA4") (class "Default")
      (node (ref "U1") (pin "P133") (pinfunction "IO_L34N_GCLK18_0_P133") (pintype "bidirectional"))
      (node (ref "U3") (pin "7") (pinfunction "A4_7") (pintype "input"))
    )
    (net (code "85") (name "/XA5") (class "Default")
      (node (ref "U1") (pin "P120") (pinfunction "IO_L62N_VREF_0_P120") (pintype "bidirectional"))
      (node (ref "U3") (pin "16") (pinfunction "A5_16") (pintype "input"))
    )
    (net (code "86") (name "/XA6") (class "Default")
      (node (ref "U1") (pin "P118") (pinfunction "IO_L63N_SCP6_0_P118") (pintype "bidirectional"))
      (node (ref "U3") (pin "17") (pinfunction "A6_17") (pintype "input"))
    )
    (net (code "87") (name "/XA7") (class "Default")
      (node (ref "U1") (pin "P116") (pinfunction "IO_L64N_SCP4_0_P116") (pintype "bidirectional"))
      (node (ref "U3") (pin "18") (pinfunction "A7_18") (pintype "input"))
    )
    (net (code "88") (name "/XA8") (class "Default")
      (node (ref "U1") (pin "P114") (pinfunction "IO_L65N_SCP2_0_P114") (pintype "bidirectional"))
      (node (ref "U3") (pin "19") (pinfunction "A8_19") (pintype "input"))
    )
    (net (code "89") (name "/XA9") (class "Default")
      (node (ref "U1") (pin "P112") (pinfunction "IO_L66P_SCP1_0_P112") (pintype "bidirectional"))
      (node (ref "U3") (pin "20") (pinfunction "A9_20") (pintype "input"))
    )
    (net (code "90") (name "/XA10") (class "Default")
      (node (ref "U1") (pin "P104") (pinfunction "IO_L1N_VREF_1_P104") (pintype "bidirectional"))
      (node (ref "U3") (pin "26") (pinfunction "A10_26") (pintype "input"))
    )
    (net (code "91") (name "/XA11") (class "Default")
      (node (ref "U1") (pin "P102") (pinfunction "IO_L32P_1_P102") (pintype "bidirectional"))
      (node (ref "U3") (pin "27") (pinfunction "A11_27") (pintype "input"))
    )
    (net (code "92") (name "/XA12") (class "Default")
      (node (ref "U1") (pin "P101") (pinfunction "IO_L32N_1_P101") (pintype "bidirectional"))
      (node (ref "U3") (pin "28") (pinfunction "A12_28") (pintype "input"))
    )
    (net (code "93") (name "/XA13") (class "Default")
      (node (ref "U1") (pin "P100") (pinfunction "IO_L33P_1_P100") (pintype "bidirectional"))
      (node (ref "U3") (pin "29") (pinfunction "A13_29") (pintype "input"))
    )
    (net (code "94") (name "/XA14") (class "Default")
      (node (ref "U1") (pin "P111") (pinfunction "IO_L66N_SCP0_0_P111") (pintype "bidirectional"))
      (node (ref "U3") (pin "30") (pinfunction "A14_30") (pintype "input"))
    )
    (net (code "95") (name "/XA15") (class "Default")
      (node (ref "U1") (pin "P131") (pinfunction "IO_L35N_GCLK16_0_P131") (pintype "bidirectional"))
      (node (ref "U3") (pin "38") (pinfunction "A15_38") (pintype "input"))
    )
    (net (code "96") (name "/XA16") (class "Default")
      (node (ref "U1") (pin "P138") (pinfunction "IO_L4P_0_P138") (pintype "bidirectional"))
      (node (ref "U3") (pin "39") (pinfunction "A16_39") (pintype "input"))
    )
    (net (code "97") (name "/XA17") (class "Default")
      (node (ref "U1") (pin "P140") (pinfunction "IO_L3P_0_P140") (pintype "bidirectional"))
      (node (ref "U3") (pin "40") (pinfunction "A17_40") (pintype "input"))
    )
    (net (code "98") (name "/XA18") (class "Default")
      (node (ref "U1") (pin "P142") (pinfunction "IO_L2P_0_P142") (pintype "bidirectional"))
      (node (ref "U3") (pin "41") (pinfunction "A18/NC_41") (pintype "input"))
    )
    (net (code "99") (name "/XA19") (class "Default")
      (node (ref "U1") (pin "P105") (pinfunction "IO_L1P_1_P105") (pintype "bidirectional"))
      (node (ref "U3") (pin "25") (pinfunction "A19/NC_25") (pintype "input"))
    )
    (net (code "100") (name "/XA20") (class "Default")
      (node (ref "U1") (pin "P143") (pinfunction "IO_L1N_VREF_0_P143") (pintype "bidirectional"))
      (node (ref "U3") (pin "42") (pinfunction "A20/NC_42") (pintype "input"))
    )
    (net (code "101") (name "/XD0") (class "Default")
      (node (ref "U1") (pin "P132") (pinfunction "IO_L35P_GCLK17_0_P132") (pintype "bidirectional"))
      (node (ref "U3") (pin "9") (pinfunction "D0_9") (pintype "bidirectional"))
    )
    (net (code "102") (name "/XD1") (class "Default")
      (node (ref "U1") (pin "P127") (pinfunction "IO_L36P_GCLK15_0_P127") (pintype "bidirectional"))
      (node (ref "U3") (pin "10") (pinfunction "D1_10") (pintype "bidirectional"))
    )
    (net (code "103") (name "/XD2") (class "Default")
      (node (ref "U1") (pin "P124") (pinfunction "IO_L37P_GCLK13_0_P124") (pintype "bidirectional"))
      (node (ref "U3") (pin "13") (pinfunction "D2_13") (pintype "bidirectional"))
    )
    (net (code "104") (name "/XD3") (class "Default")
      (node (ref "U1") (pin "P123") (pinfunction "IO_L37N_GCLK12_0_P123") (pintype "bidirectional"))
      (node (ref "U3") (pin "14") (pinfunction "D3_14") (pintype "bidirectional"))
    )
    (net (code "105") (name "/XD4") (class "Default")
      (node (ref "U1") (pin "P115") (pinfunction "IO_L65P_SCP3_0_P115") (pintype "bidirectional"))
      (node (ref "U3") (pin "31") (pinfunction "D4_31") (pintype "bidirectional"))
    )
    (net (code "106") (name "/XD5") (class "Default")
      (node (ref "U1") (pin "P117") (pinfunction "IO_L64P_SCP5_0_P117") (pintype "bidirectional"))
      (node (ref "U3") (pin "32") (pinfunction "D5_32") (pintype "bidirectional"))
    )
    (net (code "107") (name "/XD6") (class "Default")
      (node (ref "U1") (pin "P119") (pinfunction "IO_L63P_SCP7_0_P119") (pintype "bidirectional"))
      (node (ref "U3") (pin "35") (pinfunction "D6_35") (pintype "bidirectional"))
    )
    (net (code "108") (name "/XD7") (class "Default")
      (node (ref "U1") (pin "P126") (pinfunction "IO_L36N_GCLK14_0_P126") (pintype "bidirectional"))
      (node (ref "U3") (pin "36") (pinfunction "D7_36") (pintype "bidirectional"))
    )
    (net (code "109") (name "1.2V") (class "Default")
      (node (ref "C10") (pin "2") (pinfunction "2_2") (pintype "passive"))
      (node (ref "C11") (pin "2") (pinfunction "2_2") (pintype "passive"))
      (node (ref "C12") (pin "2") (pinfunction "2_2") (pintype "passive"))
      (node (ref "C13") (pin "2") (pinfunction "2_2") (pintype "passive"))
      (node (ref "C9") (pin "2") (pinfunction "2_2") (pintype "passive"))
      (node (ref "L2") (pin "2") (pinfunction "2_2") (pintype "passive"))
      (node (ref "U1") (pin "P128") (pinfunction "VCCINT_P128") (pintype "input"))
      (node (ref "U1") (pin "P19") (pinfunction "VCCINT_P19") (pintype "input"))
      (node (ref "U1") (pin "P28") (pinfunction "VCCINT_P28") (pintype "input"))
      (node (ref "U1") (pin "P52") (pinfunction "VCCINT_P52") (pintype "input"))
      (node (ref "U1") (pin "P89") (pinfunction "VCCINT_P89") (pintype "input"))
    )
    (net (code "110") (name "3.3V") (class "Default")
      (node (ref "C14") (pin "2") (pinfunction "2_2") (pintype "passive"))
      (node (ref "C15") (pin "2") (pinfunction "2_2") (pintype "passive"))
      (node (ref "C16") (pin "2") (pinfunction "2_2") (pintype "passive"))
      (node (ref "C17") (pin "2") (pinfunction "2_2") (pintype "passive"))
      (node (ref "C18") (pin "2") (pinfunction "2_2") (pintype "passive"))
      (node (ref "C19") (pin "2") (pinfunction "2_2") (pintype "passive"))
      (node (ref "C20") (pin "2") (pinfunction "2_2") (pintype "passive"))
      (node (ref "C21") (pin "2") (pinfunction "2_2") (pintype "passive"))
      (node (ref "C22") (pin "2") (pinfunction "2_2") (pintype "passive"))
      (node (ref "C23") (pin "2") (pinfunction "2_2") (pintype "passive"))
      (node (ref "C24") (pin "2") (pinfunction "2_2") (pintype "passive"))
      (node (ref "C25") (pin "2") (pinfunction "2_2") (pintype "passive"))
      (node (ref "C26") (pin "1") (pinfunction "1_1") (pintype "passive"))
      (node (ref "C27") (pin "2") (pinfunction "2_2") (pintype "passive"))
      (node (ref "J11") (pin "1") (pinfunction "1_1") (pintype "passive"))
      (node (ref "J12") (pin "12") (pinfunction "12_12") (pintype "passive"))
      (node (ref "JTAG") (pin "1") (pinfunction "S_1") (pintype "passive"))
      (node (ref "L1") (pin "2") (pinfunction "2_2") (pintype "passive"))
      (node (ref "R24") (pin "2") (pinfunction "2_2") (pintype "passive"))
      (node (ref "R27") (pin "2") (pinfunction "2_2") (pintype "passive"))
      (node (ref "R30") (pin "1") (pinfunction "1_1") (pintype "passive"))
      (node (ref "R31") (pin "2") (pinfunction "2_2") (pintype "passive"))
      (node (ref "R32") (pin "2") (pinfunction "2_2") (pintype "passive"))
      (node (ref "RGB") (pin "4") (pinfunction "S_4") (pintype "passive"))
      (node (ref "SDCARD") (pin "4") (pinfunction "VDD_4") (pintype "power_in"))
      (node (ref "U1") (pin "P103") (pinfunction "VCCO_1_P103") (pintype "input"))
      (node (ref "U1") (pin "P122") (pinfunction "VCCO_0_P122") (pintype "input"))
      (node (ref "U1") (pin "P125") (pinfunction "VCCO_0_P125") (pintype "input"))
      (node (ref "U1") (pin "P129") (pinfunction "VCCAUX_P129") (pintype "input"))
      (node (ref "U1") (pin "P135") (pinfunction "VCCO_0_P135") (pintype "input"))
      (node (ref "U1") (pin "P18") (pinfunction "VCCO_3_P18") (pintype "input"))
      (node (ref "U1") (pin "P20") (pinfunction "VCCAUX_P20") (pintype "input"))
      (node (ref "U1") (pin "P31") (pinfunction "VCCO_3_P31") (pintype "input"))
      (node (ref "U1") (pin "P36") (pinfunction "VCCAUX_P36") (pintype "input"))
      (node (ref "U1") (pin "P4") (pinfunction "VCCO_3_P4") (pintype "input"))
      (node (ref "U1") (pin "P42") (pinfunction "VCCO_2_P42") (pintype "input"))
      (node (ref "U1") (pin "P53") (pinfunction "VCCAUX_P53") (pintype "input"))
      (node (ref "U1") (pin "P63") (pinfunction "VCCO_2_P63") (pintype "input"))
      (node (ref "U1") (pin "P69") (pinfunction "IO_L1N_M0_CMPMISO_2_P69") (pintype "bidirectional"))
      (node (ref "U1") (pin "P76") (pinfunction "VCCO_1_P76") (pintype "input"))
      (node (ref "U1") (pin "P86") (pinfunction "VCCO_1_P86") (pintype "input"))
      (node (ref "U1") (pin "P90") (pinfunction "VCCAUX_P90") (pintype "input"))
      (node (ref "U2") (pin "8") (pinfunction "VCC_8") (pintype "bidirectional"))
      (node (ref "U3") (pin "11") (pinfunction "VDD_11") (pintype "input"))
      (node (ref "U3") (pin "33") (pinfunction "VDD_33") (pintype "input"))
      (node (ref "U5") (pin "4") (pinfunction "VCC_4") (pintype "power_in"))
    )
    (net (code "111") (name "5V") (class "Default")
      (node (ref "C28") (pin "1") (pinfunction "1_1") (pintype "passive"))
      (node (ref "C30") (pin "1") (pinfunction "1_1") (pintype "passive"))
      (node (ref "C32") (pin "2") (pinfunction "2_2") (pintype "passive"))
      (node (ref "C33") (pin "2") (pinfunction "2_2") (pintype "passive"))
      (node (ref "J12") (pin "1") (pinfunction "1_1") (pintype "passive"))
      (node (ref "L3") (pin "2") (pinfunction "2_2") (pintype "passive"))
      (node (ref "PS/2") (pin "4") (pinfunction "4_4") (pintype "passive"))
      (node (ref "R5") (pin "1") (pinfunction "1_1") (pintype "passive"))
      (node (ref "R7") (pin "2") (pinfunction "2_2") (pintype "passive"))
      (node (ref "U4") (pin "14") (pinfunction "DPOS_14") (pintype "bidirectional"))
      (node (ref "U4") (pin "15") (pinfunction "VSYNC_15") (pintype "bidirectional"))
      (node (ref "U4") (pin "4") (pinfunction "APOS_4") (pintype "bidirectional"))
      (node (ref "U4") (pin "5") (pinfunction "CE_5") (pintype "bidirectional"))
      (node (ref "U6") (pin "3") (pinfunction "VIN_3") (pintype "input"))
      (node (ref "U7") (pin "3") (pinfunction "VIN_3") (pintype "input"))
    )
    (net (code "112") (name "GND") (class "Default")
      (node (ref "AUDIO") (pin "SLEEVE") (pinfunction "SLEEVE_SLEEVE") (pintype "bidirectional"))
      (node (ref "C1") (pin "2") (pinfunction "2_2") (pintype "passive"))
      (node (ref "C10") (pin "1") (pinfunction "1_1") (pintype "passive"))
      (node (ref "C11") (pin "1") (pinfunction "1_1") (pintype "passive"))
      (node (ref "C12") (pin "1") (pinfunction "1_1") (pintype "passive"))
      (node (ref "C13") (pin "1") (pinfunction "1_1") (pintype "passive"))
      (node (ref "C14") (pin "1") (pinfunction "1_1") (pintype "passive"))
      (node (ref "C15") (pin "1") (pinfunction "1_1") (pintype "passive"))
      (node (ref "C16") (pin "1") (pinfunction "1_1") (pintype "passive"))
      (node (ref "C17") (pin "1") (pinfunction "1_1") (pintype "passive"))
      (node (ref "C18") (pin "1") (pinfunction "1_1") (pintype "passive"))
      (node (ref "C19") (pin "1") (pinfunction "1_1") (pintype "passive"))
      (node (ref "C2") (pin "2") (pinfunction "2_2") (pintype "passive"))
      (node (ref "C20") (pin "1") (pinfunction "1_1") (pintype "passive"))
      (node (ref "C21") (pin "1") (pinfunction "1_1") (pintype "passive"))
      (node (ref "C22") (pin "1") (pinfunction "1_1") (pintype "passive"))
      (node (ref "C23") (pin "1") (pinfunction "1_1") (pintype "passive"))
      (node (ref "C24") (pin "1") (pinfunction "1_1") (pintype "passive"))
      (node (ref "C25") (pin "1") (pinfunction "1_1") (pintype "passive"))
      (node (ref "C26") (pin "2") (pinfunction "2_2") (pintype "passive"))
      (node (ref "C27") (pin "1") (pinfunction "1_1") (pintype "passive"))
      (node (ref "C28") (pin "2") (pinfunction "2_2") (pintype "passive"))
      (node (ref "C29") (pin "2") (pinfunction "2_2") (pintype "passive"))
      (node (ref "C3") (pin "2") (pinfunction "2_2") (pintype "passive"))
      (node (ref "C30") (pin "2") (pinfunction "2_2") (pintype "passive"))
      (node (ref "C31") (pin "2") (pinfunction "2_2") (pintype "passive"))
      (node (ref "C32") (pin "1") (pinfunction "1_1") (pintype "passive"))
      (node (ref "C33") (pin "1") (pinfunction "1_1") (pintype "passive"))
      (node (ref "C4") (pin "2") (pinfunction "2_2") (pintype "passive"))
      (node (ref "C9") (pin "1") (pinfunction "1_1") (pintype "passive"))
      (node (ref "CVBS") (pin "4") (pinfunction "2_4") (pintype "passive"))
      (node (ref "D1") (pin "A") (pinfunction "A_A") (pintype "passive"))
      (node (ref "D2") (pin "K") (pinfunction "C_K") (pintype "passive"))
      (node (ref "D3") (pin "K") (pinfunction "C_K") (pintype "passive"))
      (node (ref "D4") (pin "C") (pinfunction "C_C") (pintype "passive"))
      (node (ref "D5") (pin "C") (pinfunction "C_C") (pintype "passive"))
      (node (ref "EAR") (pin "SLEEVE") (pinfunction "SLEEVE_SLEEVE") (pintype "bidirectional"))
      (node (ref "J10") (pin "12") (pinfunction "12_12") (pintype "passive"))
      (node (ref "J11") (pin "12") (pinfunction "12_12") (pintype "passive"))
      (node (ref "JOYSTICK") (pin "8") (pinfunction "8_8") (pintype "passive"))
      (node (ref "JTAG") (pin "6") (pinfunction "S_6") (pintype "passive"))
      (node (ref "PROG") (pin "1") (pinfunction "1_1") (pintype "passive"))
      (node (ref "PS/2") (pin "3") (pinfunction "3_3") (pintype "passive"))
      (node (ref "PWCON") (pin "1") (pinfunction "1_1") (pintype "passive"))
      (node (ref "PWUSB") (pin "5") (pinfunction "GND_5") (pintype "bidirectional"))
      (node (ref "R1") (pin "2") (pinfunction "2_2") (pintype "passive"))
      (node (ref "R2") (pin "2") (pinfunction "2_2") (pintype "passive"))
      (node (ref "R29") (pin "2") (pinfunction "2_2") (pintype "passive"))
      (node (ref "R3") (pin "2") (pinfunction "2_2") (pintype "passive"))
      (node (ref "RGB") (pin "1") (pinfunction "S_1") (pintype "passive"))
      (node (ref "SDCARD") (pin "3") (pinfunction "VSS1_3") (pintype "power_in"))
      (node (ref "SDCARD") (pin "6") (pinfunction "VSS2_6") (pintype "power_in"))
      (node (ref "SDCARD") (pin "M1") (pinfunction "GND_M1") (pintype "power_in"))
      (node (ref "SDCARD") (pin "M2") (pinfunction "GND_M2") (pintype "power_in"))
      (node (ref "SDCARD") (pin "M3") (pinfunction "GND_M3") (pintype "power_in"))
      (node (ref "SDCARD") (pin "M4") (pinfunction "GND_M4") (pintype "power_in"))
      (node (ref "T1") (pin "2") (pinfunction "E_2") (pintype "passive"))
      (node (ref "U1") (pin "P108") (pinfunction "GND_P108") (pintype "power_in"))
      (node (ref "U1") (pin "P113") (pinfunction "GND_P113") (pintype "power_in"))
      (node (ref "U1") (pin "P13") (pinfunction "GND_P13") (pintype "power_in"))
      (node (ref "U1") (pin "P130") (pinfunction "GND_P130") (pintype "power_in"))
      (node (ref "U1") (pin "P136") (pinfunction "GND_P136") (pintype "power_in"))
      (node (ref "U1") (pin "P144") (pinfunction "IO_L1P_HSWAPEN_0_P144") (pintype "bidirectional"))
      (node (ref "U1") (pin "P25") (pinfunction "GND_P25") (pintype "power_in"))
      (node (ref "U1") (pin "P3") (pinfunction "GND_P3") (pintype "power_in"))
      (node (ref "U1") (pin "P49") (pinfunction "GND_P49") (pintype "power_in"))
      (node (ref "U1") (pin "P54") (pinfunction "GND_P54") (pintype "power_in"))
      (node (ref "U1") (pin "P60") (pinfunction "IO_L13P_M1_2_P60") (pintype "bidirectional"))
      (node (ref "U1") (pin "P68") (pinfunction "GND_P68") (pintype "power_in"))
      (node (ref "U1") (pin "P73") (pinfunction "SUSPEND_P73") (pintype "input"))
      (node (ref "U1") (pin "P77") (pinfunction "GND_P77") (pintype "power_in"))
      (node (ref "U1") (pin "P91") (pinfunction "GND_P91") (pintype "power_in"))
      (node (ref "U1") (pin "P96") (pinfunction "GND_P96") (pintype "power_in"))
      (node (ref "U2") (pin "4") (pinfunction "GND_4") (pintype "bidirectional"))
      (node (ref "U3") (pin "12") (pinfunction "VSS_12") (pintype "input"))
      (node (ref "U3") (pin "34") (pinfunction "VSS_34") (pintype "input"))
      (node (ref "U3") (pin "37") (pinfunction "~{OE}_37") (pintype "input"))
      (node (ref "U3") (pin "8") (pinfunction "~{CS}_8") (pintype "input"))
      (node (ref "U4") (pin "12") (pinfunction "YTRAP_12") (pintype "bidirectional"))
      (node (ref "U4") (pin "13") (pinfunction "DGND_13") (pintype "bidirectional"))
      (node (ref "U4") (pin "2") (pinfunction "AGND_2") (pintype "bidirectional"))
      (node (ref "U5") (pin "2") (pinfunction "GND_2") (pintype "power_in"))
      (node (ref "U6") (pin "1") (pinfunction "GND_1") (pintype "power_in"))
      (node (ref "U7") (pin "1") (pinfunction "GND_1") (pintype "power_in"))
    )
    (net (code "113") (name "Net-(C3-Pad1)") (class "Default")
      (node (ref "C3") (pin "1") (pinfunction "1_1") (pintype "passive"))
      (node (ref "C35") (pin "1") (pinfunction "1_1") (pintype "passive"))
      (node (ref "R23") (pin "1") (pinfunction "1_1") (pintype "passive"))
    )
    (net (code "114") (name "Net-(C5-Pad2)") (class "Default")
      (node (ref "C5") (pin "2") (pinfunction "2_2") (pintype "passive"))
      (node (ref "R15") (pin "2") (pinfunction "2_2") (pintype "passive"))
    )
    (net (code "115") (name "Net-(C34-Pad1)") (class "Default")
      (node (ref "C34") (pin "1") (pinfunction "1_1") (pintype "passive"))
      (node (ref "C4") (pin "1") (pinfunction "1_1") (pintype "passive"))
      (node (ref "R22") (pin "1") (pinfunction "1_1") (pintype "passive"))
    )
    (net (code "116") (name "Net-(C36-Pad-)") (class "Default")
      (node (ref "C36") (pin "-") (pinfunction "-_-") (pintype "passive"))
      (node (ref "R4") (pin "1") (pinfunction "1_1") (pintype "passive"))
    )
    (net (code "117") (name "Net-(CVBS-1)") (class "Default")
      (node (ref "CVBS") (pin "3") (pinfunction "1_3") (pintype "passive"))
      (node (ref "R4") (pin "2") (pinfunction "2_2") (pintype "passive"))
    )
    (net (code "118") (name "Net-(D1-C)") (class "Default")
      (node (ref "C2") (pin "1") (pinfunction "1_1") (pintype "passive"))
      (node (ref "C5") (pin "1") (pinfunction "1_1") (pintype "passive"))
      (node (ref "D1") (pin "K") (pinfunction "C_K") (pintype "passive"))
      (node (ref "R28") (pin "1") (pinfunction "1_1") (pintype "passive"))
    )
    (net (code "119") (name "Net-(D2-PadA)") (class "Default")
      (node (ref "D2") (pin "A") (pinfunction "A_A") (pintype "passive"))
      (node (ref "R25") (pin "2") (pinfunction "2_2") (pintype "passive"))
      (node (ref "Y1") (pin "1") (pinfunction "1_1") (pintype "passive"))
    )
    (net (code "120") (name "Net-(D3-PadA)") (class "Default")
      (node (ref "D3") (pin "A") (pinfunction "A_A") (pintype "passive"))
      (node (ref "R26") (pin "1") (pinfunction "1_1") (pintype "passive"))
      (node (ref "Y2") (pin "1") (pinfunction "1_1") (pintype "passive"))
    )
    (net (code "121") (name "Net-(D4-PadA)") (class "Default")
      (node (ref "D4") (pin "A") (pinfunction "A_A") (pintype "passive"))
      (node (ref "R6") (pin "1") (pinfunction "1_1") (pintype "passive"))
    )
    (net (code "122") (name "Net-(D5-PadA)") (class "Default")
      (node (ref "D5") (pin "A") (pinfunction "A_A") (pintype "passive"))
      (node (ref "R7") (pin "1") (pinfunction "1_1") (pintype "passive"))
    )
    (net (code "123") (name "Net-(EAR-LEFT)") (class "Default")
      (node (ref "EAR") (pin "TIP") (pinfunction "LEFT_TIP") (pintype "bidirectional"))
      (node (ref "R15") (pin "1") (pinfunction "1_1") (pintype "passive"))
      (node (ref "R29") (pin "1") (pinfunction "1_1") (pintype "passive"))
    )
    (net (code "124") (name "Net-(JOYSTICK-Pad7)") (class "Default")
      (node (ref "JOYSTICK") (pin "7") (pinfunction "7_7") (pintype "passive"))
      (node (ref "R5") (pin "2") (pinfunction "2_2") (pintype "passive"))
    )
    (net (code "125") (name "Net-(L3-Pad1)") (class "Default")
      (node (ref "L3") (pin "1") (pinfunction "1_1") (pintype "passive"))
      (node (ref "SW") (pin "1") (pinfunction "1_1") (pintype "passive"))
    )
    (net (code "126") (name "Net-(PS/2-Pad1)") (class "Default")
      (node (ref "PS/2") (pin "1") (pinfunction "1_1") (pintype "passive"))
      (node (ref "R8") (pin "1") (pinfunction "1_1") (pintype "passive"))
    )
    (net (code "127") (name "Net-(PS/2-Pad2)") (class "Default")
      (node (ref "PS/2") (pin "2") (pinfunction "2_2") (pintype "passive"))
      (node (ref "R9") (pin "1") (pinfunction "1_1") (pintype "passive"))
    )
    (net (code "128") (name "Net-(PS/2-Pad5)") (class "Default")
      (node (ref "PS/2") (pin "5") (pinfunction "5_5") (pintype "passive"))
      (node (ref "R10") (pin "1") (pinfunction "1_1") (pintype "passive"))
    )
    (net (code "129") (name "Net-(PS/2-Pad6)") (class "Default")
      (node (ref "PS/2") (pin "6") (pinfunction "6_6") (pintype "passive"))
      (node (ref "R11") (pin "1") (pinfunction "1_1") (pintype "passive"))
    )
    (net (code "130") (name "Net-(PWUSB-VCC)") (class "Default")
      (node (ref "PWCON") (pin "2") (pinfunction "2_2") (pintype "passive"))
      (node (ref "PWUSB") (pin "1") (pinfunction "VCC_1") (pintype "bidirectional"))
      (node (ref "SW") (pin "2") (pinfunction "2_2") (pintype "passive"))
    )
    (net (code "131") (name "Net-(SDCARD-DAT1)") (class "Default")
      (node (ref "R31") (pin "1") (pinfunction "1_1") (pintype "passive"))
      (node (ref "SDCARD") (pin "8") (pinfunction "DAT1_8") (pintype "bidirectional"))
    )
    (net (code "132") (name "Net-(SDCARD-DAT2)") (class "Default")
      (node (ref "R32") (pin "1") (pinfunction "1_1") (pintype "passive"))
      (node (ref "SDCARD") (pin "9") (pinfunction "DAT2_9") (pintype "bidirectional"))
    )
    (net (code "133") (name "Net-(T1-B)") (class "Default")
      (node (ref "R28") (pin "2") (pinfunction "2_2") (pintype "passive"))
      (node (ref "T1") (pin "1") (pinfunction "B_1") (pintype "passive"))
    )
    (net (code "134") (name "Net-(U1C-PROGRAM_B_2)") (class "Default")
      (node (ref "PROG") (pin "2") (pinfunction "2_2") (pintype "passive"))
      (node (ref "R24") (pin "1") (pinfunction "1_1") (pintype "passive"))
      (node (ref "U1") (pin "P37") (pinfunction "PROGRAM_B_2_P37") (pintype "input"))
    )
    (net (code "135") (name "Net-(U4-4FSC)") (class "Default")
      (node (ref "C1") (pin "1") (pinfunction "1_1") (pintype "passive"))
      (node (ref "U4") (pin "3") (pinfunction "4FSC_3") (pintype "bidirectional"))
      (node (ref "Y1") (pin "2") (pinfunction "2_2") (pintype "passive"))
      (node (ref "Y2") (pin "2") (pinfunction "2_2") (pintype "passive"))
    )
    (net (code "136") (name "Net-(U4-BIN)") (class "Default")
      (node (ref "C8") (pin "1") (pinfunction "1_1") (pintype "passive"))
      (node (ref "U4") (pin "8") (pinfunction "BIN_8") (pintype "bidirectional"))
    )
    (net (code "137") (name "Net-(U4-COMP)") (class "Default")
      (node (ref "C36") (pin "+") (pinfunction "+_+") (pintype "passive"))
      (node (ref "U4") (pin "10") (pinfunction "COMP_10") (pintype "bidirectional"))
    )
    (net (code "138") (name "Net-(U4-GIN)") (class "Default")
      (node (ref "C7") (pin "1") (pinfunction "1_1") (pintype "passive"))
      (node (ref "U4") (pin "7") (pinfunction "GIN_7") (pintype "bidirectional"))
    )
    (net (code "139") (name "Net-(U4-RIN)") (class "Default")
      (node (ref "C6") (pin "1") (pinfunction "1_1") (pintype "passive"))
      (node (ref "U4") (pin "6") (pinfunction "RIN_6") (pintype "bidirectional"))
    )
    (net (code "140") (name "Net-(U6-VOUT)") (class "Default")
      (node (ref "C29") (pin "1") (pinfunction "1_1") (pintype "passive"))
      (node (ref "L1") (pin "1") (pinfunction "1_1") (pintype "passive"))
      (node (ref "U6") (pin "2") (pinfunction "VOUT_2") (pintype "output"))
    )
    (net (code "141") (name "Net-(U7-VOUT)") (class "Default")
      (node (ref "C31") (pin "1") (pinfunction "1_1") (pintype "passive"))
      (node (ref "L2") (pin "1") (pinfunction "1_1") (pintype "passive"))
      (node (ref "U7") (pin "2") (pinfunction "VOUT_2") (pintype "output"))
    )
    (net (code "142") (name "unconnected-(EAR-RIGHT-PadRING)") (class "Default")
      (node (ref "EAR") (pin "RING") (pinfunction "RIGHT_RING") (pintype "bidirectional"))
    )
    (net (code "143") (name "unconnected-(JOYSTICK-Pad5)") (class "Default")
      (node (ref "JOYSTICK") (pin "5") (pinfunction "5_5") (pintype "passive"))
    )
    (net (code "144") (name "unconnected-(PWUSB-D+-Pad3)") (class "Default")
      (node (ref "PWUSB") (pin "3") (pinfunction "D+_3") (pintype "bidirectional"))
    )
    (net (code "145") (name "unconnected-(PWUSB-D--Pad2)") (class "Default")
      (node (ref "PWUSB") (pin "2") (pinfunction "D-_2") (pintype "bidirectional"))
    )
    (net (code "146") (name "unconnected-(PWUSB-ID-Pad4)") (class "Default")
      (node (ref "PWUSB") (pin "4") (pinfunction "ID_4") (pintype "bidirectional"))
    )
    (net (code "147") (name "unconnected-(PWUSB-SHIELD-Pad6)") (class "Default")
      (node (ref "PWUSB") (pin "6") (pinfunction "SHIELD_6") (pintype "bidirectional"))
    )
    (net (code "148") (name "unconnected-(SDCARD-CDI#-Pad10)") (class "Default")
      (node (ref "SDCARD") (pin "10") (pinfunction "CDI#_10") (pintype "output"))
    )
    (net (code "149") (name "unconnected-(SDCARD-WP-Pad11)") (class "Default")
      (node (ref "SDCARD") (pin "11") (pinfunction "WP_11") (pintype "output"))
    )
    (net (code "150") (name "unconnected-(U1C-CMPCS_B_2-PadP72)") (class "Default")
      (node (ref "U1") (pin "P72") (pinfunction "CMPCS_B_2_P72") (pintype "bidirectional"))
    )
    (net (code "151") (name "unconnected-(U1C-DONE_2-PadP71)") (class "Default")
      (node (ref "U1") (pin "P71") (pinfunction "DONE_2_P71") (pintype "bidirectional"))
    )
    (net (code "152") (name "unconnected-(U4-CRMA-Pad9)") (class "Default")
      (node (ref "U4") (pin "9") (pinfunction "CRMA_9") (pintype "bidirectional"))
    )
    (net (code "153") (name "unconnected-(U4-LUMA-Pad11)") (class "Default")
      (node (ref "U4") (pin "11") (pinfunction "LUMA_11") (pintype "bidirectional"))
    )
    (net (code "154") (name "unconnected-(U5-E{slash}D-Pad1)") (class "Default")
      (node (ref "U5") (pin "1") (pinfunction "E/D_1") (pintype "input"))
    )
  )
)
